# SiLPA_CPCIS_Con_P1_P6.net
KiCad netlist of a schematic drawn in Altium Designer
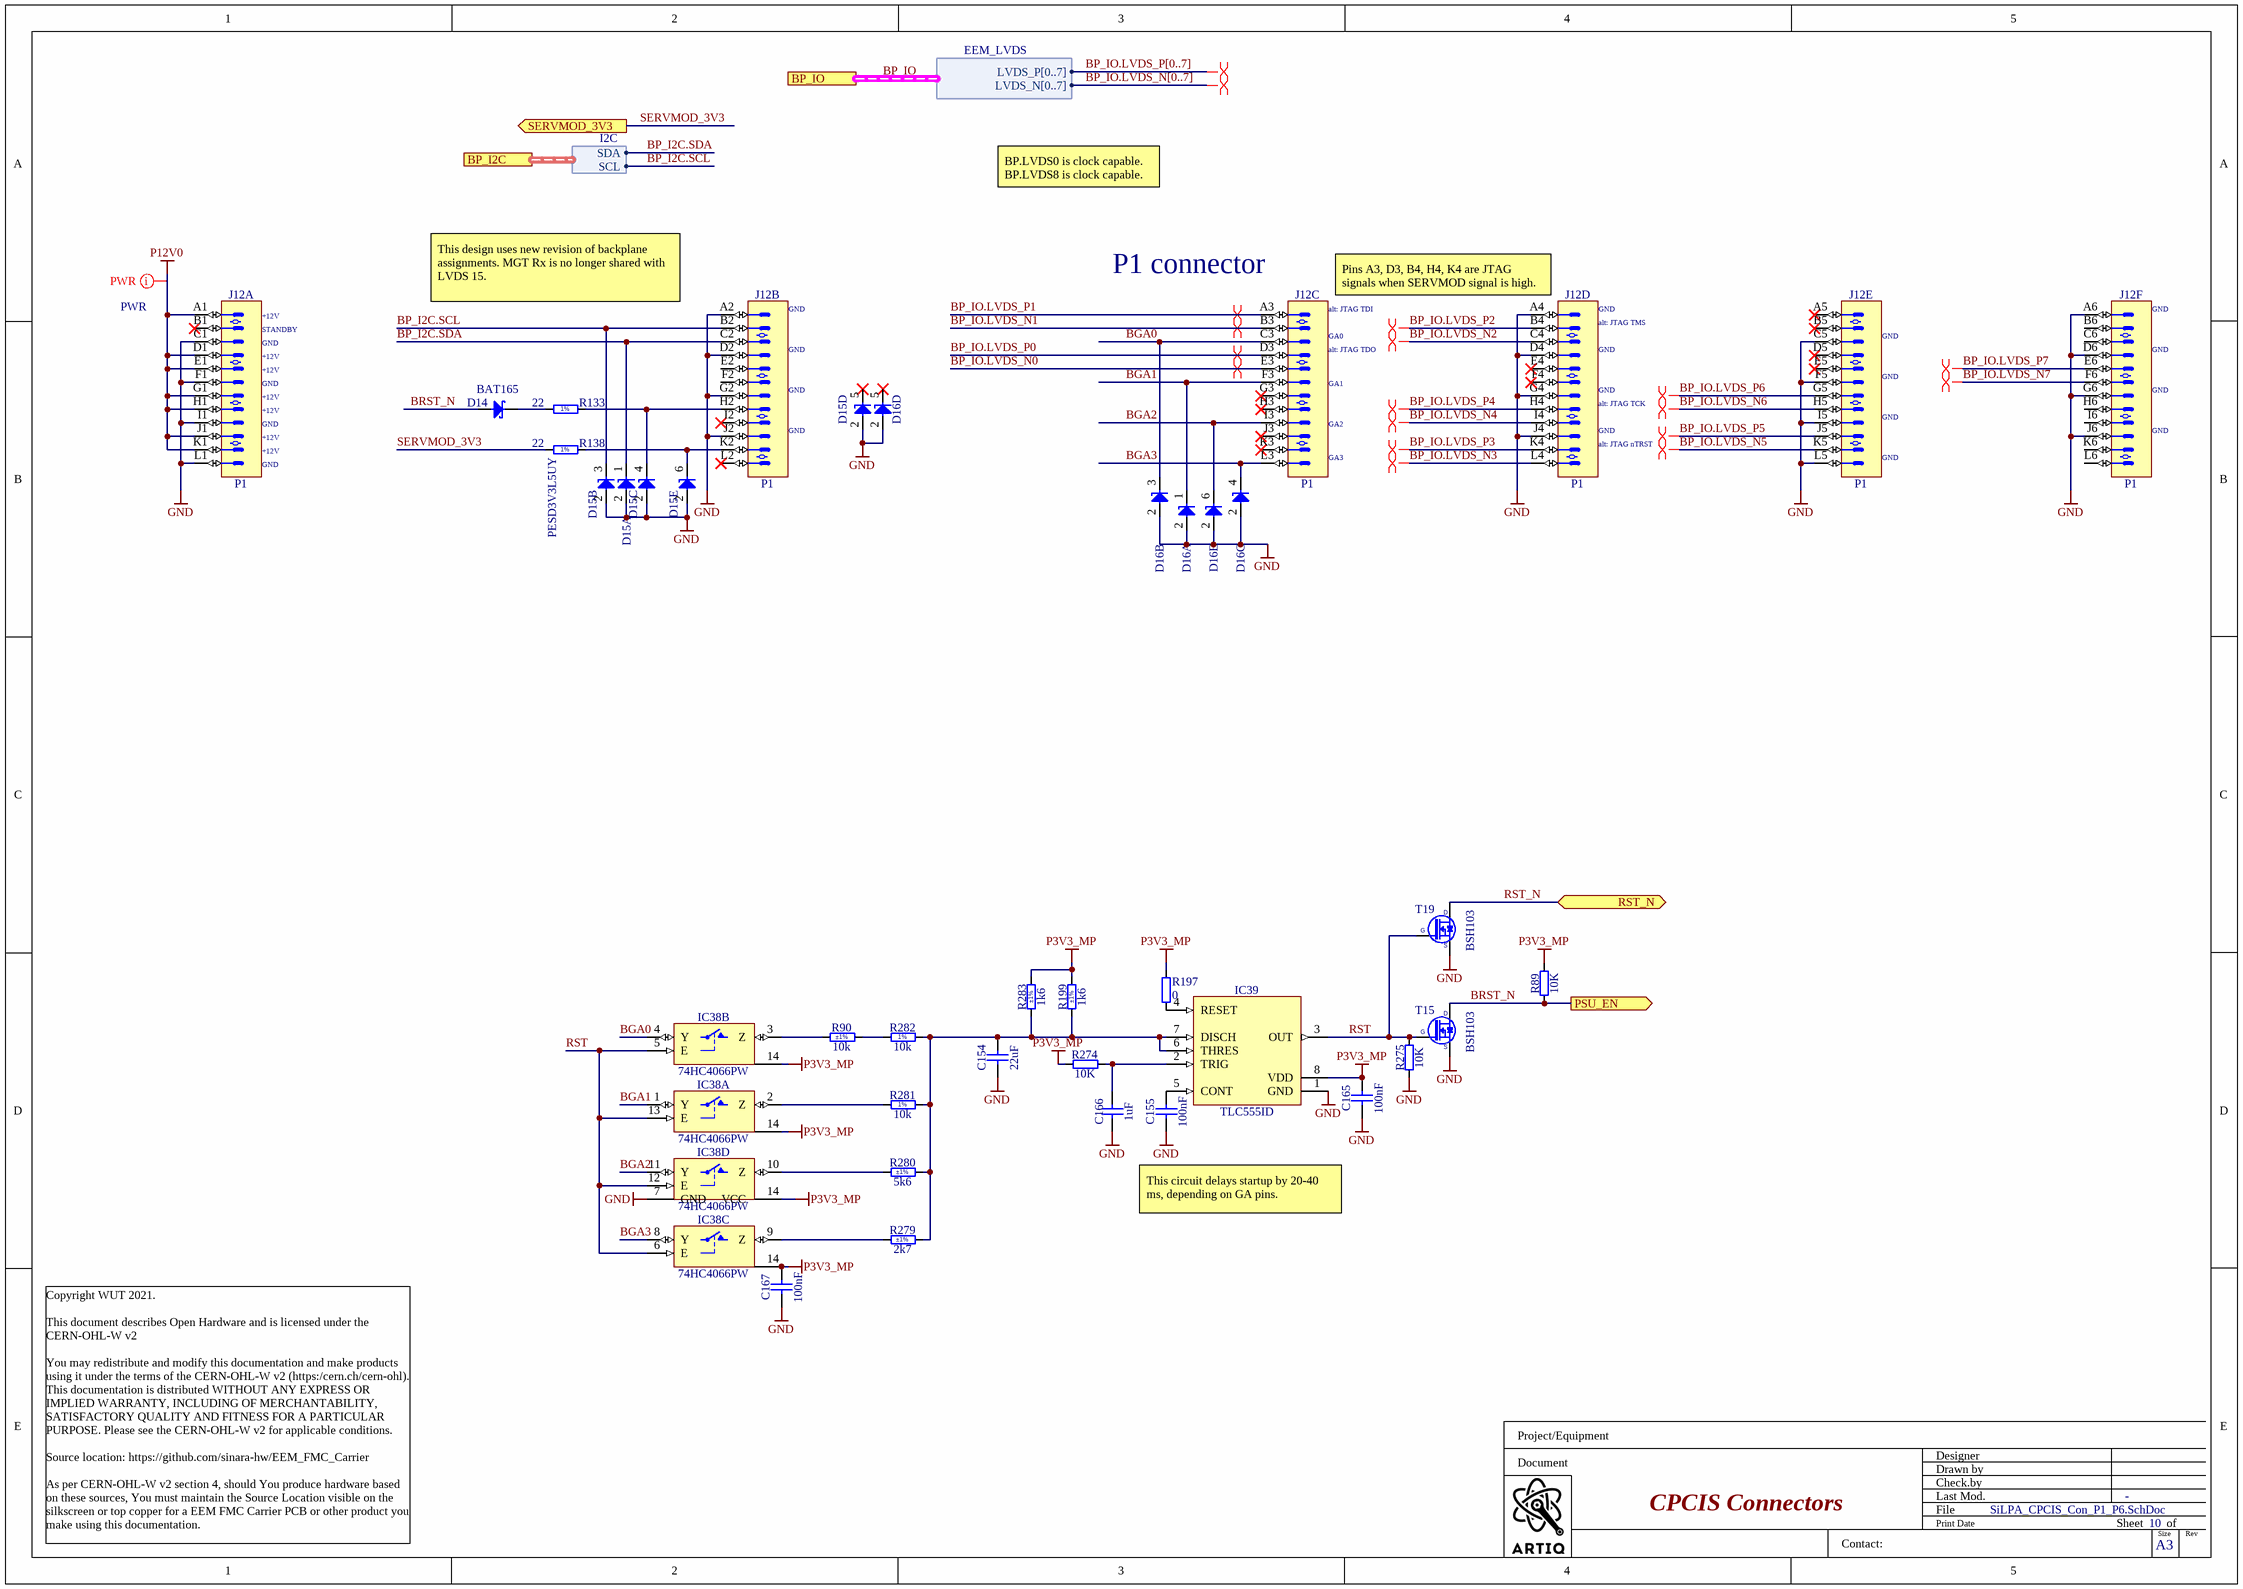
[diagram p0: SiLPA_CPCIS_Con_P1_P6.SchDoc]

(export (version "E")
  (design (tool "Eeschema 10.0.6"))
  (components
    (comp (ref "C154")
      (value "22uF")
      (footprint "CAPC1608X90N")
      (description "Non-polarised capacitor")
      (fields
        (field (name "MANUFACTURER") "GENERIC")
        (field (name "PART NUMBER") "CC0603_22UF_6.3V_20%_X5R")
        (field (name "AUTHOR") "CERN DEM JLC")
      )
      (libsource (lib "EEM_FMC_Carrier") (part "Capacitor - non polarized"))
    )
    (comp (ref "C155")
      (value "100nF")
      (footprint "CAPC1005X55N")
      (description "Non-polarised capacitor")
      (fields
        (field (name "PART NUMBER") "CC0402_100NF_16V_10%_X5R")
        (field (name "VOLTAGE") "16V")
        (field (name "AUTHOR") "CERN DEM JLC")
      )
      (libsource (lib "EEM_FMC_Carrier") (part "Capacitor - non polarized"))
    )
    (comp (ref "C165")
      (value "100nF")
      (footprint "CAPC1005X55N")
      (description "Non-polarised capacitor")
      (fields
        (field (name "PART NUMBER") "CC0402_100NF_16V_10%_X5R")
        (field (name "VOLTAGE") "16V")
        (field (name "AUTHOR") "CERN DEM JLC")
      )
      (libsource (lib "EEM_FMC_Carrier") (part "Capacitor - non polarized"))
    )
    (comp (ref "C166")
      (value "1uF")
      (footprint "CAPC1005X55N")
      (description "Non-polarised capacitor")
      (fields
        (field (name "PART NUMBER") "CC0402_1UF_16V_10%_X5R")
        (field (name "VOLTAGE") "16V")
        (field (name "AUTHOR") "CERN DEM JLC")
      )
      (libsource (lib "EEM_FMC_Carrier") (part "Capacitor - non polarized"))
    )
    (comp (ref "C167")
      (value "100nF")
      (footprint "CAPC1005X55N")
      (description "Non-polarised capacitor")
      (fields
        (field (name "PART NUMBER") "CC0402_100NF_16V_10%_X5R")
        (field (name "VOLTAGE") "16V")
        (field (name "AUTHOR") "CERN DEM JLC")
      )
      (libsource (lib "EEM_FMC_Carrier") (part "Capacitor - non polarized"))
    )
    (comp (ref "D14")
      (value "BAT165")
      (footprint "SOD2512X110N")
      (description "Schottky Diode")
      (fields
        (field (name "MANUFACTURER") "INFINEON")
        (field (name "VOLTAGE") "40V")
        (field (name "AUTHOR") "CERN DEM JLC")
      )
      (libsource (lib "EEM_FMC_Carrier") (part "Diode Schottky"))
    )
    (comp (ref "D15")
      (value "PESD3V3L5UY")
      (footprint "SOT65P210X110-6N")
      (description "Fivefold ESD Protection Diode Arrays")
      (fields
        (field (name "VOLTAGE") "3.3V")
        (field (name "POWER") "200W")
        (field (name "AUTHOR") "CERN DEM WB")
      )
      (libsource (lib "EEM_FMC_Carrier") (part "PESD Array 5diodes 6pins Common anode2"))
    )
    (comp (ref "D16")
      (value "PESD3V3L5UY")
      (footprint "SOT65P210X110-6N")
      (description "Fivefold ESD Protection Diode Arrays")
      (fields
        (field (name "VOLTAGE") "3.3V")
        (field (name "POWER") "200W")
        (field (name "AUTHOR") "CERN DEM WB")
      )
      (libsource (lib "EEM_FMC_Carrier") (part "PESD Array 5diodes 6pins Common anode2"))
    )
    (comp (ref "IC38")
      (value "74HC4066PW")
      (footprint "SOP65P640X110-14N")
      (fields (field (name "MANUFACTURER") "NXP SEMICONDUCTORS") (field (name "AUTHOR") "CERN DEM JLC"))
      (libsource (lib "EEM_FMC_Carrier") (part "4066"))
    )
    (comp (ref "IC39")
      (value "TLC555ID")
      (footprint "SOIC127P600X175-8N")
      (description "LinCMOS Timer")
      (fields (field (name "MANUFACTURER") "TEXAS INSTRUMENTS") (field (name "AUTHOR") "CERN DEM JMW"))
      (libsource (lib "EEM_FMC_Carrier") (part "TLC555"))
    )
    (comp (ref "J12")
      (value "P1")
      (footprint "AMPHENOL_10052825-101LF")
      (description "72 Contacts Header, 6 Columns, 4 Pairs per Column")
      (fields
        (field (name "PART NUMBER") "AMPHENOL_10052825-101LF")
        (field (name "MANUFACTURER") "AMPHENOL")
        (field (name "AUTHOR") "CERN DEM MR")
      )
      (libsource (lib "EEM_FMC_Carrier") (part "AMPHENOL_10052825-101LF"))
    )
    (comp (ref "R89")
      (value "10K")
      (footprint "RESC1005X40N")
      (description "Resistor - 1%")
      (fields
        (field (name "PART NUMBER") "R0402_10K_1%_0.0625W_100PPM")
        (field (name "POWER") "0.0625W")
        (field (name "AUTHOR") "CERN DEM JLC")
      )
      (libsource (lib "EEM_FMC_Carrier") (part "Resistor - 1%"))
    )
    (comp (ref "R90")
      (value "10k")
      (footprint "RESC1005X40N")
      (description "Resistor - 1%")
      (fields
        (field (name "PART NUMBER") "R0402_10K_1%_0.0625W_100PPM")
        (field (name "POWER") "0.0625W")
        (field (name "TOLERANCE") "±1%")
        (field (name "AUTHOR") "CERN DEM JLC")
      )
      (libsource (lib "EEM_FMC_Carrier") (part "Resistor - 1%"))
    )
    (comp (ref "R133")
      (value "22")
      (footprint "RESC1005X40N")
      (description "Resistor - 1%")
      (fields
        (field (name "PART NUMBER") "R0402_22R_1%_0.0625W_100PPM")
        (field (name "POWER") "0.0625W")
        (field (name "AUTHOR") "CERN DEM JLC")
      )
      (libsource (lib "EEM_FMC_Carrier") (part "Resistor - 1%"))
    )
    (comp (ref "R138")
      (value "22")
      (footprint "RESC1005X40N")
      (description "Resistor - 1%")
      (fields
        (field (name "PART NUMBER") "R0402_22R_1%_0.0625W_100PPM")
        (field (name "POWER") "0.0625W")
        (field (name "AUTHOR") "CERN DEM JLC")
      )
      (libsource (lib "EEM_FMC_Carrier") (part "Resistor - 1%"))
    )
    (comp (ref "R197")
      (value "0")
      (footprint "RESC1005X40N")
      (description "Resistor")
      (fields
        (field (name "PART NUMBER") "R0402_0R_JUMPER")
        (field (name "MANUFACTURER") "GENERIC")
        (field (name "AUTHOR") "CERN DEM JLC")
      )
      (libsource (lib "EEM_FMC_Carrier") (part "Resistor"))
    )
    (comp (ref "R199")
      (value "1k6")
      (footprint "RESC1005X40N")
      (description "Resistor - 1%")
      (fields
        (field (name "PART NUMBER") "R0402_1K6_1%_0.0625W_100PPM")
        (field (name "POWER") "0.0625W")
        (field (name "TOLERANCE") "±1%")
        (field (name "AUTHOR") "CERN DEM JLC")
      )
      (libsource (lib "EEM_FMC_Carrier") (part "Resistor - 1%"))
    )
    (comp (ref "R274")
      (value "10K")
      (footprint "RESC1005X40N")
      (description "Resistor - 1%")
      (fields
        (field (name "PART NUMBER") "R0402_10K_1%_0.0625W_100PPM")
        (field (name "POWER") "0.0625W")
        (field (name "AUTHOR") "CERN DEM JLC")
      )
      (libsource (lib "EEM_FMC_Carrier") (part "Resistor - 1%"))
    )
    (comp (ref "R275")
      (value "10K")
      (footprint "RESC1005X40N")
      (description "Resistor - 1%")
      (fields
        (field (name "PART NUMBER") "R0402_10K_1%_0.0625W_100PPM")
        (field (name "POWER") "0.0625W")
        (field (name "AUTHOR") "CERN DEM JLC")
      )
      (libsource (lib "EEM_FMC_Carrier") (part "Resistor - 1%"))
    )
    (comp (ref "R279")
      (value "2k7")
      (footprint "RESC1608X55N")
      (description "Resistor - 1%")
      (fields
        (field (name "PART NUMBER") "R0603_2K7_1%_0.1W_100PPM")
        (field (name "POWER") "0.1W")
        (field (name "TOLERANCE") "±1%")
        (field (name "AUTHOR") "CERN DEM JLC")
      )
      (libsource (lib "") (part "Resistor - 1%_1"))
    )
    (comp (ref "R280")
      (value "5k6")
      (footprint "RESC1005X40N")
      (description "Resistor - 1%")
      (fields
        (field (name "PART NUMBER") "R0402_5K6_1%_0.0625W_100PPM")
        (field (name "POWER") "0.0625W")
        (field (name "TOLERANCE") "±1%")
        (field (name "AUTHOR") "CERN DEM JLC")
      )
      (libsource (lib "EEM_FMC_Carrier") (part "Resistor - 1%"))
    )
    (comp (ref "R281")
      (value "10k")
      (footprint "RESC1005X40N")
      (description "Resistor - 1%")
      (fields
        (field (name "PART NUMBER") "R0402_1K_1%_0.0625W_100PPM")
        (field (name "POWER") "0.0625W")
        (field (name "AUTHOR") "CERN DEM JLC")
      )
      (libsource (lib "EEM_FMC_Carrier") (part "Resistor - 1%"))
    )
    (comp (ref "R282")
      (value "10k")
      (footprint "RESC1005X40N")
      (description "Resistor - 1%")
      (fields
        (field (name "PART NUMBER") "R0402_1K_1%_0.0625W_100PPM")
        (field (name "POWER") "0.0625W")
        (field (name "AUTHOR") "CERN DEM JLC")
      )
      (libsource (lib "EEM_FMC_Carrier") (part "Resistor - 1%"))
    )
    (comp (ref "R283")
      (value "1k6")
      (footprint "RESC1005X40N")
      (description "Resistor - 1%")
      (fields
        (field (name "PART NUMBER") "R0402_1K6_1%_0.0625W_100PPM")
        (field (name "POWER") "0.0625W")
        (field (name "TOLERANCE") "±1%")
        (field (name "AUTHOR") "CERN DEM JLC")
      )
      (libsource (lib "EEM_FMC_Carrier") (part "Resistor - 1%"))
    )
    (comp (ref "T15")
      (value "BSH103")
      (footprint "SOT95P230X110-3N")
      (description "N-CHANNEL MOSFET WITH DIODE")
      (fields (field (name "MANUFACTURER") "NEXPERIA") (field (name "AUTHOR") "CERN DEM JLC"))
      (libsource (lib "EEM_FMC_Carrier") (part "N-MOSFET-D 1G 2S 3D"))
    )
    (comp (ref "T19")
      (value "BSH103")
      (footprint "SOT95P230X110-3N")
      (description "N-CHANNEL MOSFET WITH DIODE")
      (fields (field (name "MANUFACTURER") "NEXPERIA") (field (name "AUTHOR") "CERN DEM JLC"))
      (libsource (lib "EEM_FMC_Carrier") (part "N-MOSFET-D 1G 2S 3D"))
    )
  )
  (nets
    (net (code "3") (name "/BGA0") (class "Default")
      (node (ref "D16") (pin "3") (pinfunction "C_3") (pintype "passive"))
      (node (ref "IC38") (pin "4") (pinfunction "Y_4") (pintype "bidirectional"))
      (node (ref "J12") (pin "C3") (pinfunction "C3_C3") (pintype "bidirectional"))
    )
    (net (code "4") (name "/BGA1") (class "Default")
      (node (ref "D16") (pin "1") (pinfunction "C_1") (pintype "passive"))
      (node (ref "IC38") (pin "1") (pinfunction "Y_1") (pintype "bidirectional"))
      (node (ref "J12") (pin "F3") (pinfunction "F3_F3") (pintype "bidirectional"))
    )
    (net (code "5") (name "/BGA2") (class "Default")
      (node (ref "D16") (pin "6") (pinfunction "C_6") (pintype "passive"))
      (node (ref "IC38") (pin "11") (pinfunction "Y_11") (pintype "bidirectional"))
      (node (ref "J12") (pin "I3") (pinfunction "I3_I3") (pintype "bidirectional"))
    )
    (net (code "6") (name "/BGA3") (class "Default")
      (node (ref "D16") (pin "4") (pinfunction "C_4") (pintype "passive"))
      (node (ref "IC38") (pin "8") (pinfunction "Y_8") (pintype "bidirectional"))
      (node (ref "J12") (pin "L3") (pinfunction "L3_L3") (pintype "bidirectional"))
    )
    (net (code "7") (name "/BP_I2C.SCL") (class "Default")
      (node (ref "D15") (pin "3") (pinfunction "C_3") (pintype "passive"))
      (node (ref "J12") (pin "B2") (pinfunction "B2_B2") (pintype "bidirectional"))
    )
    (net (code "8") (name "/BP_I2C.SDA") (class "Default")
      (node (ref "D15") (pin "1") (pinfunction "C_1") (pintype "passive"))
      (node (ref "J12") (pin "C2") (pinfunction "C2_C2") (pintype "bidirectional"))
    )
    (net (code "9") (name "/BP_IO.LVDS_N0") (class "Default")
      (node (ref "J12") (pin "E3") (pinfunction "E3_E3") (pintype "bidirectional"))
    )
    (net (code "10") (name "/BP_IO.LVDS_N1") (class "Default")
      (node (ref "J12") (pin "B3") (pinfunction "B3_B3") (pintype "bidirectional"))
    )
    (net (code "11") (name "/BP_IO.LVDS_N2") (class "Default")
      (node (ref "J12") (pin "C4") (pinfunction "C4_C4") (pintype "bidirectional"))
    )
    (net (code "12") (name "/BP_IO.LVDS_N3") (class "Default")
      (node (ref "J12") (pin "L4") (pinfunction "L4_L4") (pintype "bidirectional"))
    )
    (net (code "13") (name "/BP_IO.LVDS_N4") (class "Default")
      (node (ref "J12") (pin "I4") (pinfunction "I4_I4") (pintype "bidirectional"))
    )
    (net (code "14") (name "/BP_IO.LVDS_N5") (class "Default")
      (node (ref "J12") (pin "K5") (pinfunction "K5_K5") (pintype "bidirectional"))
    )
    (net (code "15") (name "/BP_IO.LVDS_N6") (class "Default")
      (node (ref "J12") (pin "H5") (pinfunction "H5_H5") (pintype "bidirectional"))
    )
    (net (code "16") (name "/BP_IO.LVDS_N7") (class "Default")
      (node (ref "J12") (pin "F6") (pinfunction "F6_F6") (pintype "bidirectional"))
    )
    (net (code "18") (name "/BP_IO.LVDS_P0") (class "Default")
      (node (ref "J12") (pin "D3") (pinfunction "D3_D3") (pintype "bidirectional"))
    )
    (net (code "19") (name "/BP_IO.LVDS_P1") (class "Default")
      (node (ref "J12") (pin "A3") (pinfunction "A3_A3") (pintype "bidirectional"))
    )
    (net (code "20") (name "/BP_IO.LVDS_P2") (class "Default")
      (node (ref "J12") (pin "B4") (pinfunction "B4_B4") (pintype "bidirectional"))
    )
    (net (code "21") (name "/BP_IO.LVDS_P3") (class "Default")
      (node (ref "J12") (pin "K4") (pinfunction "K4_K4") (pintype "bidirectional"))
    )
    (net (code "22") (name "/BP_IO.LVDS_P4") (class "Default")
      (node (ref "J12") (pin "H4") (pinfunction "H4_H4") (pintype "bidirectional"))
    )
    (net (code "23") (name "/BP_IO.LVDS_P5") (class "Default")
      (node (ref "J12") (pin "J5") (pinfunction "J5_J5") (pintype "bidirectional"))
    )
    (net (code "24") (name "/BP_IO.LVDS_P6") (class "Default")
      (node (ref "J12") (pin "G5") (pinfunction "G5_G5") (pintype "bidirectional"))
    )
    (net (code "25") (name "/BP_IO.LVDS_P7") (class "Default")
      (node (ref "J12") (pin "E6") (pinfunction "E6_E6") (pintype "bidirectional"))
    )
    (net (code "28") (name "/BRST_N") (class "Default")
      (node (ref "D14") (pin "2") (pinfunction "A_2") (pintype "passive"))
      (node (ref "R89") (pin "1") (pinfunction "1_1") (pintype "passive"))
      (node (ref "T15") (pin "3") (pinfunction "D_3") (pintype "passive"))
    )
    (net (code "29") (name "/RST") (class "Default")
      (node (ref "IC38") (pin "12") (pinfunction "E_12") (pintype "input"))
      (node (ref "IC38") (pin "13") (pinfunction "E_13") (pintype "input"))
      (node (ref "IC38") (pin "5") (pinfunction "E_5") (pintype "input"))
      (node (ref "IC38") (pin "6") (pinfunction "E_6") (pintype "input"))
      (node (ref "IC39") (pin "3") (pinfunction "OUT_3") (pintype "output"))
      (node (ref "R275") (pin "2") (pinfunction "2_2") (pintype "passive"))
      (node (ref "T15") (pin "1") (pinfunction "G_1") (pintype "passive"))
      (node (ref "T19") (pin "1") (pinfunction "G_1") (pintype "passive"))
    )
    (net (code "30") (name "/RST_N") (class "Default")
      (node (ref "T19") (pin "3") (pinfunction "D_3") (pintype "passive"))
    )
    (net (code "31") (name "/SERVMOD_3V3") (class "Default")
      (node (ref "R138") (pin "1") (pinfunction "1_1") (pintype "passive"))
    )
    (net (code "33") (name "GND") (class "Default")
      (node (ref "C154") (pin "1") (pinfunction "1_1") (pintype "passive"))
      (node (ref "C155") (pin "1") (pinfunction "1_1") (pintype "passive"))
      (node (ref "C165") (pin "1") (pinfunction "1_1") (pintype "passive"))
      (node (ref "C166") (pin "1") (pinfunction "1_1") (pintype "passive"))
      (node (ref "C167") (pin "1") (pinfunction "1_1") (pintype "passive"))
      (node (ref "D15") (pin "2") (pinfunction "A_2") (pintype "passive"))
      (node (ref "D16") (pin "2") (pinfunction "A_2") (pintype "passive"))
      (node (ref "IC38") (pin "7") (pinfunction "GND_7") (pintype "power_in"))
      (node (ref "IC39") (pin "1") (pinfunction "GND_1") (pintype "power_in"))
      (node (ref "J12") (pin "A2") (pinfunction "A2_A2") (pintype "bidirectional"))
      (node (ref "J12") (pin "A4") (pinfunction "A4_A4") (pintype "bidirectional"))
      (node (ref "J12") (pin "A6") (pinfunction "A6_A6") (pintype "bidirectional"))
      (node (ref "J12") (pin "C1") (pinfunction "C1_C1") (pintype "bidirectional"))
      (node (ref "J12") (pin "C5") (pinfunction "C5_C5") (pintype "bidirectional"))
      (node (ref "J12") (pin "D2") (pinfunction "D2_D2") (pintype "bidirectional"))
      (node (ref "J12") (pin "D4") (pinfunction "D4_D4") (pintype "bidirectional"))
      (node (ref "J12") (pin "D6") (pinfunction "D6_D6") (pintype "bidirectional"))
      (node (ref "J12") (pin "F1") (pinfunction "F1_F1") (pintype "bidirectional"))
      (node (ref "J12") (pin "F5") (pinfunction "F5_F5") (pintype "bidirectional"))
      (node (ref "J12") (pin "G2") (pinfunction "G2_G2") (pintype "bidirectional"))
      (node (ref "J12") (pin "G4") (pinfunction "G4_G4") (pintype "bidirectional"))
      (node (ref "J12") (pin "G6") (pinfunction "G6_G6") (pintype "bidirectional"))
      (node (ref "J12") (pin "I1") (pinfunction "I1_I1") (pintype "bidirectional"))
      (node (ref "J12") (pin "I5") (pinfunction "I5_I5") (pintype "bidirectional"))
      (node (ref "J12") (pin "J2") (pinfunction "J2_J2") (pintype "bidirectional"))
      (node (ref "J12") (pin "J4") (pinfunction "J4_J4") (pintype "bidirectional"))
      (node (ref "J12") (pin "J6") (pinfunction "J6_J6") (pintype "bidirectional"))
      (node (ref "J12") (pin "L1") (pinfunction "L1_L1") (pintype "bidirectional"))
      (node (ref "J12") (pin "L5") (pinfunction "L5_L5") (pintype "bidirectional"))
      (node (ref "R275") (pin "1") (pinfunction "1_1") (pintype "passive"))
      (node (ref "T15") (pin "2") (pinfunction "S_2") (pintype "passive"))
      (node (ref "T19") (pin "2") (pinfunction "S_2") (pintype "passive"))
    )
    (net (code "34") (name "Net-(D14-C)") (class "Default")
      (node (ref "D14") (pin "1") (pinfunction "C_1") (pintype "passive"))
      (node (ref "R133") (pin "1") (pinfunction "1_1") (pintype "passive"))
    )
    (net (code "35") (name "Net-(D15C-C)") (class "Default")
      (node (ref "D15") (pin "4") (pinfunction "C_4") (pintype "passive"))
      (node (ref "J12") (pin "H2") (pinfunction "H2_H2") (pintype "bidirectional"))
      (node (ref "R133") (pin "2") (pinfunction "2_2") (pintype "passive"))
    )
    (net (code "36") (name "Net-(D15E-C)") (class "Default")
      (node (ref "D15") (pin "6") (pinfunction "C_6") (pintype "passive"))
      (node (ref "J12") (pin "K2") (pinfunction "K2_K2") (pintype "bidirectional"))
      (node (ref "R138") (pin "2") (pinfunction "2_2") (pintype "passive"))
    )
    (net (code "37") (name "Net-(IC38A-Z)") (class "Default")
      (node (ref "IC38") (pin "2") (pinfunction "Z_2") (pintype "bidirectional"))
      (node (ref "R281") (pin "1") (pinfunction "1_1") (pintype "passive"))
    )
    (net (code "38") (name "Net-(IC38B-Z)") (class "Default")
      (node (ref "IC38") (pin "3") (pinfunction "Z_3") (pintype "bidirectional"))
      (node (ref "R90") (pin "1") (pinfunction "1_1") (pintype "passive"))
    )
    (net (code "39") (name "Net-(IC38C-Z)") (class "Default")
      (node (ref "IC38") (pin "9") (pinfunction "Z_9") (pintype "bidirectional"))
      (node (ref "R279") (pin "1") (pinfunction "1_1") (pintype "passive"))
    )
    (net (code "40") (name "Net-(IC38D-Z)") (class "Default")
      (node (ref "IC38") (pin "10") (pinfunction "Z_10") (pintype "bidirectional"))
      (node (ref "R280") (pin "1") (pinfunction "1_1") (pintype "passive"))
    )
    (net (code "41") (name "Net-(IC39-CONT)") (class "Default")
      (node (ref "C155") (pin "2") (pinfunction "2_2") (pintype "passive"))
      (node (ref "IC39") (pin "5") (pinfunction "CONT_5") (pintype "input"))
    )
    (net (code "42") (name "Net-(IC39-DISCH)") (class "Default")
      (node (ref "C154") (pin "2") (pinfunction "2_2") (pintype "passive"))
      (node (ref "IC39") (pin "6") (pinfunction "THRES_6") (pintype "input"))
      (node (ref "IC39") (pin "7") (pinfunction "DISCH_7") (pintype "input"))
      (node (ref "R199") (pin "1") (pinfunction "1_1") (pintype "passive"))
      (node (ref "R279") (pin "2") (pinfunction "2_2") (pintype "passive"))
      (node (ref "R280") (pin "2") (pinfunction "2_2") (pintype "passive"))
      (node (ref "R281") (pin "2") (pinfunction "2_2") (pintype "passive"))
      (node (ref "R282") (pin "2") (pinfunction "2_2") (pintype "passive"))
      (node (ref "R283") (pin "1") (pinfunction "1_1") (pintype "passive"))
    )
    (net (code "43") (name "Net-(IC39-RESET)") (class "Default")
      (node (ref "IC39") (pin "4") (pinfunction "RESET_4") (pintype "input"))
      (node (ref "R197") (pin "1") (pinfunction "1_1") (pintype "passive"))
    )
    (net (code "44") (name "Net-(IC39-TRIG)") (class "Default")
      (node (ref "C166") (pin "2") (pinfunction "2_2") (pintype "passive"))
      (node (ref "IC39") (pin "2") (pinfunction "TRIG_2") (pintype "input"))
      (node (ref "R274") (pin "2") (pinfunction "2_2") (pintype "passive"))
    )
    (net (code "45") (name "Net-(R282-Pad1)") (class "Default")
      (node (ref "R282") (pin "1") (pinfunction "1_1") (pintype "passive"))
      (node (ref "R90") (pin "2") (pinfunction "2_2") (pintype "passive"))
    )
    (net (code "46") (name "P3V3_MP") (class "Default")
      (node (ref "C165") (pin "2") (pinfunction "2_2") (pintype "passive"))
      (node (ref "C167") (pin "2") (pinfunction "2_2") (pintype "passive"))
      (node (ref "IC38") (pin "14") (pinfunction "VCC_14") (pintype "power_in"))
      (node (ref "IC39") (pin "8") (pinfunction "VDD_8") (pintype "power_in"))
      (node (ref "R197") (pin "2") (pinfunction "2_2") (pintype "passive"))
      (node (ref "R199") (pin "2") (pinfunction "2_2") (pintype "passive"))
      (node (ref "R274") (pin "1") (pinfunction "1_1") (pintype "passive"))
      (node (ref "R283") (pin "2") (pinfunction "2_2") (pintype "passive"))
      (node (ref "R89") (pin "2") (pinfunction "2_2") (pintype "passive"))
    )
    (net (code "47") (name "P12V0") (class "Default")
      (node (ref "J12") (pin "A1") (pinfunction "A1_A1") (pintype "bidirectional"))
      (node (ref "J12") (pin "D1") (pinfunction "D1_D1") (pintype "bidirectional"))
      (node (ref "J12") (pin "E1") (pinfunction "E1_E1") (pintype "bidirectional"))
      (node (ref "J12") (pin "G1") (pinfunction "G1_G1") (pintype "bidirectional"))
      (node (ref "J12") (pin "H1") (pinfunction "H1_H1") (pintype "bidirectional"))
      (node (ref "J12") (pin "J1") (pinfunction "J1_J1") (pintype "bidirectional"))
      (node (ref "J12") (pin "K1") (pinfunction "K1_K1") (pintype "bidirectional"))
    )
    (net (code "48") (name "unconnected-(D15D-C-Pad5)") (class "Default")
      (node (ref "D15") (pin "5") (pinfunction "C_5") (pintype "passive+no_connect"))
    )
    (net (code "49") (name "unconnected-(D16D-C-Pad5)") (class "Default")
      (node (ref "D16") (pin "5") (pinfunction "C_5") (pintype "passive+no_connect"))
    )
    (net (code "50") (name "unconnected-(J12-PadA5)") (class "Default")
      (node (ref "J12") (pin "A5") (pinfunction "A5_A5") (pintype "bidirectional+no_connect"))
    )
    (net (code "51") (name "unconnected-(J12-PadB1)") (class "Default")
      (node (ref "J12") (pin "B1") (pinfunction "B1_B1") (pintype "bidirectional+no_connect"))
    )
    (net (code "52") (name "unconnected-(J12-PadB5)") (class "Default")
      (node (ref "J12") (pin "B5") (pinfunction "B5_B5") (pintype "bidirectional+no_connect"))
    )
    (net (code "53") (name "unconnected-(J12-PadB6)") (class "Default")
      (node (ref "J12") (pin "B6") (pinfunction "B6_B6") (pintype "bidirectional"))
    )
    (net (code "54") (name "unconnected-(J12-PadC6)") (class "Default")
      (node (ref "J12") (pin "C6") (pinfunction "C6_C6") (pintype "bidirectional"))
    )
    (net (code "55") (name "unconnected-(J12-PadD5)") (class "Default")
      (node (ref "J12") (pin "D5") (pinfunction "D5_D5") (pintype "bidirectional+no_connect"))
    )
    (net (code "56") (name "unconnected-(J12-PadE2)") (class "Default")
      (node (ref "J12") (pin "E2") (pinfunction "E2_E2") (pintype "bidirectional"))
    )
    (net (code "57") (name "unconnected-(J12-PadE4)") (class "Default")
      (node (ref "J12") (pin "E4") (pinfunction "E4_E4") (pintype "bidirectional+no_connect"))
    )
    (net (code "58") (name "unconnected-(J12-PadE5)") (class "Default")
      (node (ref "J12") (pin "E5") (pinfunction "E5_E5") (pintype "bidirectional+no_connect"))
    )
    (net (code "59") (name "unconnected-(J12-PadF2)") (class "Default")
      (node (ref "J12") (pin "F2") (pinfunction "F2_F2") (pintype "bidirectional"))
    )
    (net (code "60") (name "unconnected-(J12-PadF4)") (class "Default")
      (node (ref "J12") (pin "F4") (pinfunction "F4_F4") (pintype "bidirectional+no_connect"))
    )
    (net (code "61") (name "unconnected-(J12-PadG3)") (class "Default")
      (node (ref "J12") (pin "G3") (pinfunction "G3_G3") (pintype "bidirectional+no_connect"))
    )
    (net (code "62") (name "unconnected-(J12-PadH3)") (class "Default")
      (node (ref "J12") (pin "H3") (pinfunction "H3_H3") (pintype "bidirectional+no_connect"))
    )
    (net (code "63") (name "unconnected-(J12-PadH6)") (class "Default")
      (node (ref "J12") (pin "H6") (pinfunction "H6_H6") (pintype "bidirectional"))
    )
    (net (code "64") (name "unconnected-(J12-PadI2)") (class "Default")
      (node (ref "J12") (pin "I2") (pinfunction "I2_I2") (pintype "bidirectional+no_connect"))
    )
    (net (code "65") (name "unconnected-(J12-PadI6)") (class "Default")
      (node (ref "J12") (pin "I6") (pinfunction "I6_I6") (pintype "bidirectional"))
    )
    (net (code "66") (name "unconnected-(J12-PadJ3)") (class "Default")
      (node (ref "J12") (pin "J3") (pinfunction "J3_J3") (pintype "bidirectional+no_connect"))
    )
    (net (code "67") (name "unconnected-(J12-PadK3)") (class "Default")
      (node (ref "J12") (pin "K3") (pinfunction "K3_K3") (pintype "bidirectional+no_connect"))
    )
    (net (code "68") (name "unconnected-(J12-PadK6)") (class "Default")
      (node (ref "J12") (pin "K6") (pinfunction "K6_K6") (pintype "bidirectional"))
    )
    (net (code "69") (name "unconnected-(J12-PadL2)") (class "Default")
      (node (ref "J12") (pin "L2") (pinfunction "L2_L2") (pintype "bidirectional+no_connect"))
    )
    (net (code "70") (name "unconnected-(J12-PadL6)") (class "Default")
      (node (ref "J12") (pin "L6") (pinfunction "L6_L6") (pintype "bidirectional"))
    )
  )
)
